# BMS_FETs.net
KiCad netlist of a schematic drawn in Altium Designer
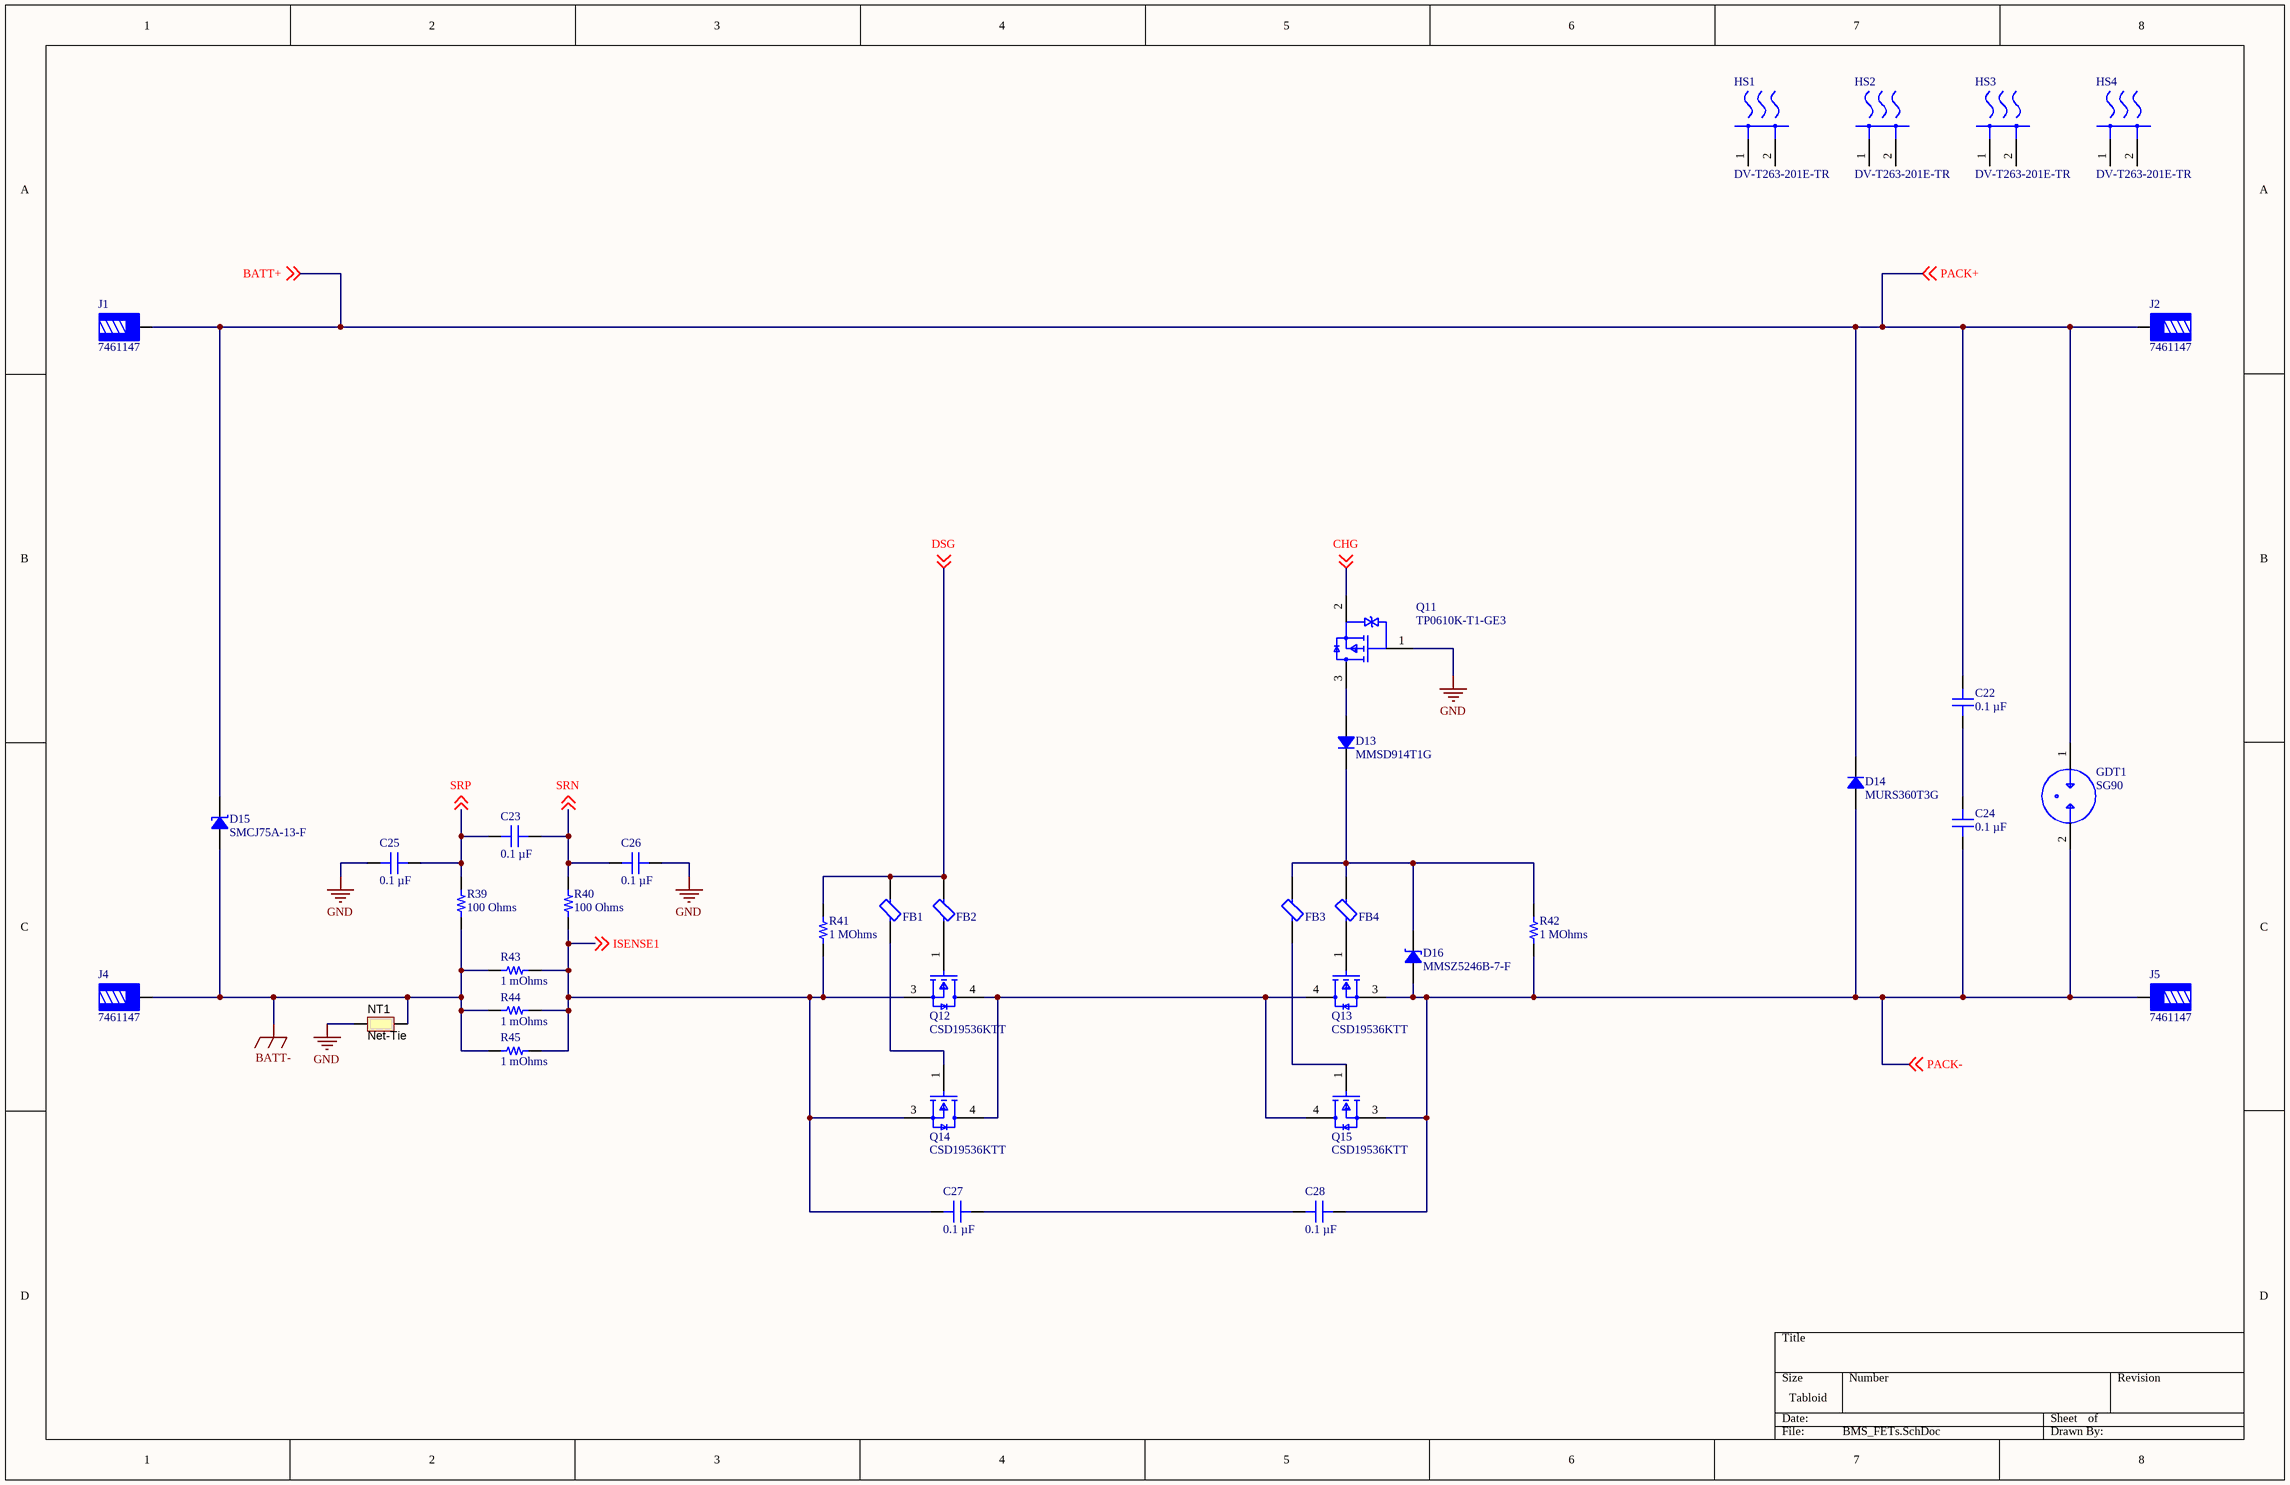
[diagram p0: BMS_FETs.SchDoc]

(export (version "E")
  (design (tool "Eeschema 10.0.6"))
  (components
    (comp (ref "C22")
      (value "0.1 µF")
      (footprint "MURATA GRM188 0603_1608")
      (description "CAP CER 0.1UF 100V X7R 0603")
      (fields
        (field (name "PART NUMBER") "GRM188R72A104KA35D")
        (field (name "CAPACITANCE") "0.1 µF")
        (field (name "MANUFACTURER") "Murata Electronics")
      )
      (libsource (lib "Celestial Altium Library - altium_library") (part "Capacitor"))
    )
    (comp (ref "C23")
      (value "0.1 µF")
      (footprint "CAP 0603_1608")
      (description "CAP CER 0.1UF 50V X7R 0603")
      (fields
        (field (name "PART NUMBER") "885012206095")
        (field (name "CAPACITANCE") "0.1 µF")
        (field (name "MANUFACTURER") "Würth Elektronik")
      )
      (libsource (lib "Celestial Altium Library - altium_library") (part "Capacitor"))
    )
    (comp (ref "C24")
      (value "0.1 µF")
      (footprint "MURATA GRM188 0603_1608")
      (description "CAP CER 0.1UF 100V X7R 0603")
      (fields
        (field (name "PART NUMBER") "GRM188R72A104KA35D")
        (field (name "CAPACITANCE") "0.1 µF")
        (field (name "MANUFACTURER") "Murata Electronics")
      )
      (libsource (lib "Celestial Altium Library - altium_library") (part "Capacitor"))
    )
    (comp (ref "C25")
      (value "0.1 µF")
      (footprint "CAP 0603_1608")
      (description "CAP CER 0.1UF 50V X7R 0603")
      (fields
        (field (name "PART NUMBER") "885012206095")
        (field (name "CAPACITANCE") "0.1 µF")
        (field (name "MANUFACTURER") "Würth Elektronik")
      )
      (libsource (lib "Celestial Altium Library - altium_library") (part "Capacitor"))
    )
    (comp (ref "C26")
      (value "0.1 µF")
      (footprint "CAP 0603_1608")
      (description "CAP CER 0.1UF 50V X7R 0603")
      (fields
        (field (name "PART NUMBER") "885012206095")
        (field (name "CAPACITANCE") "0.1 µF")
        (field (name "MANUFACTURER") "Würth Elektronik")
      )
      (libsource (lib "Celestial Altium Library - altium_library") (part "Capacitor"))
    )
    (comp (ref "C27")
      (value "0.1 µF")
      (footprint "CAP 1206_3216 - 0.8MM")
      (description "CAP CER 0.1UF 200V X7R 1206")
      (fields
        (field (name "PART NUMBER") "885342208002")
        (field (name "CAPACITANCE") "0.1 µF")
        (field (name "MANUFACTURER") "Würth Elektronik")
      )
      (libsource (lib "Celestial Altium Library - altium_library") (part "Capacitor"))
    )
    (comp (ref "C28")
      (value "0.1 µF")
      (footprint "CAP 1206_3216 - 0.8MM")
      (description "CAP CER 0.1UF 200V X7R 1206")
      (fields
        (field (name "PART NUMBER") "885342208002")
        (field (name "CAPACITANCE") "0.1 µF")
        (field (name "MANUFACTURER") "Würth Elektronik")
      )
      (libsource (lib "Celestial Altium Library - altium_library") (part "Capacitor"))
    )
    (comp (ref "D13")
      (value "MMSD914T1G")
      (footprint "SOD-123")
      (description "DIODE GEN PURP 100V 200MA SOD123")
      (fields (field (name "MANUFACTURER") "ON Semiconductor"))
      (libsource (lib "Celestial Altium Library - altium_library") (part "Diode"))
    )
    (comp (ref "D14")
      (value "MURS360T3G")
      (footprint "DO214AB SMC")
      (description "DIODE GEN PURP 600V 3A SMC")
      (fields (field (name "MANUFACTURER") "ON Semiconductor"))
      (libsource (lib "Celestial Altium Library - altium_library") (part "Diode"))
    )
    (comp (ref "D15")
      (value "SMCJ75A-13-F")
      (footprint "DO214AB SMC")
      (description "TVS DIODE 75VWM 121VC SMC")
      (fields (field (name "MANUFACTURER") "Diodes Incorporated"))
      (libsource (lib "Celestial Altium Library - altium_library") (part "DIODE TVS UNI"))
    )
    (comp (ref "D16")
      (value "MMSZ5246B-7-F")
      (footprint "SOD-123")
      (description "DIODE ZENER 16V 500MW SOD123")
      (fields (field (name "MANUFACTURER") "Diodes Incorporated") (field (name "TOLERANCE") "±5%"))
      (libsource (lib "Celestial Altium Library - altium_library") (part "Diode Zener"))
    )
    (comp (ref "FB1")
      (value "BLM18SG221TN1D")
      (footprint "FP-BLM18-0_15-t0_5-IPC_C")
      (description "Chip Ferrite Bead, 0603, 220Ω @ 100MHz, 25%, 0.04Ω, 2.5A")
      (fields (field (name "TOLERANCE") "25%"))
      (libsource (lib "BMS_FETs") (part "BLM18SG221TN1D"))
    )
    (comp (ref "FB2")
      (value "BLM18SG221TN1D")
      (footprint "FP-BLM18-0_15-t0_5-IPC_C")
      (description "Chip Ferrite Bead, 0603, 220Ω @ 100MHz, 25%, 0.04Ω, 2.5A")
      (fields (field (name "TOLERANCE") "25%"))
      (libsource (lib "BMS_FETs") (part "BLM18SG221TN1D"))
    )
    (comp (ref "FB3")
      (value "BLM18SG221TN1D")
      (footprint "FP-BLM18-0_15-t0_5-IPC_C")
      (description "Chip Ferrite Bead, 0603, 220Ω @ 100MHz, 25%, 0.04Ω, 2.5A")
      (fields (field (name "TOLERANCE") "25%"))
      (libsource (lib "BMS_FETs") (part "BLM18SG221TN1D"))
    )
    (comp (ref "FB4")
      (value "BLM18SG221TN1D")
      (footprint "FP-BLM18-0_15-t0_5-IPC_C")
      (description "Chip Ferrite Bead, 0603, 220Ω @ 100MHz, 25%, 0.04Ω, 2.5A")
      (fields (field (name "TOLERANCE") "25%"))
      (libsource (lib "BMS_FETs") (part "BLM18SG221TN1D"))
    )
    (comp (ref "GDT1")
      (value "SG90")
      (footprint "FP-SG-MFG")
      (description "GDT 90V 2KA 2 POLE SURFACE MOUNT")
      (libsource (lib "BMS_MCU") (part "SG90"))
    )
    (comp (ref "HS1")
      (value "DV-T263-201E-TR")
      (footprint "FP-DV-T263-201E-TR-MFG")
      (description "HEATSINK FOR TO-263")
      (libsource (lib "BMS_FETs") (part "DV-T263-201E-TR"))
    )
    (comp (ref "HS2")
      (value "DV-T263-201E-TR")
      (footprint "FP-DV-T263-201E-TR-MFG")
      (description "HEATSINK FOR TO-263")
      (libsource (lib "BMS_FETs") (part "DV-T263-201E-TR"))
    )
    (comp (ref "HS3")
      (value "DV-T263-201E-TR")
      (footprint "FP-DV-T263-201E-TR-MFG")
      (description "HEATSINK FOR TO-263")
      (libsource (lib "BMS_FETs") (part "DV-T263-201E-TR"))
    )
    (comp (ref "HS4")
      (value "DV-T263-201E-TR")
      (footprint "FP-DV-T263-201E-TR-MFG")
      (description "HEATSINK FOR TO-263")
      (libsource (lib "BMS_FETs") (part "DV-T263-201E-TR"))
    )
    (comp (ref "J1")
      (value "7461147")
      (footprint "7461147_chemical surface")
      (description "7461147 REDCUBE Power Element Poles, 180A, Press-Fit, M5 Internal Thread, Vertical, WP-BUFU")
      (libsource (lib "BMS_FETs") (part "7461147"))
    )
    (comp (ref "J2")
      (value "7461147")
      (footprint "7461147_chemical surface")
      (description "7461147 REDCUBE Power Element Poles, 180A, Press-Fit, M5 Internal Thread, Vertical, WP-BUFU")
      (libsource (lib "BMS_FETs") (part "7461147"))
    )
    (comp (ref "J4")
      (value "7461147")
      (footprint "7461147_chemical surface")
      (description "7461147 REDCUBE Power Element Poles, 180A, Press-Fit, M5 Internal Thread, Vertical, WP-BUFU")
      (libsource (lib "BMS_FETs") (part "7461147"))
    )
    (comp (ref "J5")
      (value "7461147")
      (footprint "7461147_chemical surface")
      (description "7461147 REDCUBE Power Element Poles, 180A, Press-Fit, M5 Internal Thread, Vertical, WP-BUFU")
      (libsource (lib "BMS_FETs") (part "7461147"))
    )
    (comp (ref "NT1")
      (value "Net-Tie")
      (footprint "Net-Tie_10mil")
      (description "Single point connection between nets.")
      (fields (field (name "SYMBOLCREATOR") "codlsc") (field (name "PUBLISHER") "Texas Instruments"))
      (libsource (lib "BMS_FETs") (part "Net-Tie"))
    )
    (comp (ref "Q11")
      (value "TP0610K-T1-GE3")
      (footprint "FP-S-03946-IPC_C")
      (description "MOSFET P-CH 60V 185MA SOT23-3")
      (libsource (lib "BMS_FETs") (part "TP0610K-T1-GE3"))
    )
    (comp (ref "Q12")
      (value "CSD19536KTT")
      (footprint "FP-CSD19536KTT-MFG")
      (description "MOSFET N-CH 100V 200A TO263")
      (fields
        (field (name "MANUFACTURER") "Texas Instruments")
        (field (name "OCTOPART") "https://octopart.com/csd19536ktt-texas+instruments-57155051")
      )
      (libsource (lib "BMS_FETs") (part "CSD19536KTT"))
    )
    (comp (ref "Q13")
      (value "CSD19536KTT")
      (footprint "FP-CSD19536KTT-MFG")
      (description "MOSFET N-CH 100V 200A TO263")
      (fields
        (field (name "MANUFACTURER") "Texas Instruments")
        (field (name "OCTOPART") "https://octopart.com/csd19536ktt-texas+instruments-57155051")
      )
      (libsource (lib "BMS_FETs") (part "CSD19536KTT"))
    )
    (comp (ref "Q14")
      (value "CSD19536KTT")
      (footprint "FP-CSD19536KTT-MFG")
      (description "MOSFET N-CH 100V 200A TO263")
      (fields
        (field (name "MANUFACTURER") "Texas Instruments")
        (field (name "OCTOPART") "https://octopart.com/csd19536ktt-texas+instruments-57155051")
      )
      (libsource (lib "BMS_FETs") (part "CSD19536KTT"))
    )
    (comp (ref "Q15")
      (value "CSD19536KTT")
      (footprint "FP-CSD19536KTT-MFG")
      (description "MOSFET N-CH 100V 200A TO263")
      (fields
        (field (name "MANUFACTURER") "Texas Instruments")
        (field (name "OCTOPART") "https://octopart.com/csd19536ktt-texas+instruments-57155051")
      )
      (libsource (lib "BMS_FETs") (part "CSD19536KTT"))
    )
    (comp (ref "R39")
      (value "100 Ohms")
      (footprint "RES 0805_2012")
      (description "RES SMD 100 OHM 1% 1/8W 0805")
      (fields (field (name "PART NUMBER") "CRCW0805100RFKEA") (field (name "MANUFACTURER") "Vishay Dale"))
      (libsource (lib "Celestial Altium Library - altium_library") (part "Resistor"))
    )
    (comp (ref "R40")
      (value "100 Ohms")
      (footprint "RES 0805_2012")
      (description "RES SMD 100 OHM 1% 1/8W 0805")
      (fields (field (name "PART NUMBER") "CRCW0805100RFKEA") (field (name "MANUFACTURER") "Vishay Dale"))
      (libsource (lib "Celestial Altium Library - altium_library") (part "Resistor"))
    )
    (comp (ref "R41")
      (value "1 MOhms")
      (footprint "RES 0603_1608")
      (description "RES 1M OHM 5% 1/10W 0603")
      (fields
        (field (name "PART NUMBER") "RMCF0603JT1M00")
        (field (name "MANUFACTURER") "Stackpole Electronics Inc")
      )
      (libsource (lib "Celestial Altium Library - altium_library") (part "Resistor"))
    )
    (comp (ref "R42")
      (value "1 MOhms")
      (footprint "RES 0603_1608")
      (description "RES 1M OHM 5% 1/10W 0603")
      (fields
        (field (name "PART NUMBER") "RMCF0603JT1M00")
        (field (name "MANUFACTURER") "Stackpole Electronics Inc")
      )
      (libsource (lib "Celestial Altium Library - altium_library") (part "Resistor"))
    )
    (comp (ref "R43")
      (value "1 mOhms")
      (footprint "RES 2512_6432")
      (description "RES 0.001 OHM 1% 5W 2512")
      (fields (field (name "PART NUMBER") "WSLF25121L000FEA") (field (name "MANUFACTURER") "Vishay Dale"))
      (libsource (lib "Celestial Altium Library - altium_library") (part "Resistor"))
    )
    (comp (ref "R44")
      (value "1 mOhms")
      (footprint "RES 2512_6432")
      (description "RES 0.001 OHM 1% 5W 2512")
      (fields (field (name "PART NUMBER") "WSLF25121L000FEA") (field (name "MANUFACTURER") "Vishay Dale"))
      (libsource (lib "Celestial Altium Library - altium_library") (part "Resistor"))
    )
    (comp (ref "R45")
      (value "1 mOhms")
      (footprint "RES 2512_6432")
      (description "RES 0.001 OHM 1% 5W 2512")
      (fields (field (name "PART NUMBER") "WSLF25121L000FEA") (field (name "MANUFACTURER") "Vishay Dale"))
      (libsource (lib "Celestial Altium Library - altium_library") (part "Resistor"))
    )
  )
  (nets
    (net (code "1") (name "BATT+") (class "Default")
      (node (ref "C22") (pin "2") (pinfunction "2_2") (pintype "passive"))
      (node (ref "D14") (pin "2") (pinfunction "2_2") (pintype "passive"))
      (node (ref "D15") (pin "2") (pinfunction "2_2") (pintype "passive"))
      (node (ref "GDT1") (pin "1") (pinfunction "1_1") (pintype "passive"))
      (node (ref "J1") (pin "1") (pinfunction "1_1") (pintype "passive"))
      (node (ref "J2") (pin "1") (pinfunction "1_1") (pintype "passive"))
    )
    (net (code "2") (name "BATT-") (class "Default")
      (node (ref "D15") (pin "1") (pinfunction "1_1") (pintype "passive"))
      (node (ref "J4") (pin "1") (pinfunction "1_1") (pintype "passive"))
      (node (ref "NT1") (pin "2") (pinfunction "2_2") (pintype "passive"))
      (node (ref "R39") (pin "1") (pinfunction "1_1") (pintype "passive"))
      (node (ref "R43") (pin "1") (pinfunction "1_1") (pintype "passive"))
      (node (ref "R44") (pin "1") (pinfunction "1_1") (pintype "passive"))
      (node (ref "R45") (pin "1") (pinfunction "1_1") (pintype "passive"))
    )
    (net (code "3") (name "CHG") (class "Default")
      (node (ref "Q11") (pin "2") (pinfunction "S_2") (pintype "passive"))
    )
    (net (code "4") (name "DSG") (class "Default")
      (node (ref "FB1") (pin "2") (pinfunction "2_2") (pintype "passive"))
      (node (ref "FB2") (pin "2") (pinfunction "2_2") (pintype "passive"))
      (node (ref "R41") (pin "2") (pinfunction "2_2") (pintype "passive"))
    )
    (net (code "5") (name "GND") (class "Default")
      (node (ref "C25") (pin "1") (pinfunction "1_1") (pintype "passive"))
      (node (ref "C26") (pin "2") (pinfunction "2_2") (pintype "passive"))
      (node (ref "NT1") (pin "1") (pinfunction "1_1") (pintype "passive"))
      (node (ref "Q11") (pin "1") (pinfunction "G_1") (pintype "passive"))
    )
    (net (code "6") (name "ISENSE1") (class "Default")
      (node (ref "C27") (pin "1") (pinfunction "1_1") (pintype "passive"))
      (node (ref "Q12") (pin "3") (pinfunction "Source_3") (pintype "passive"))
      (node (ref "Q14") (pin "3") (pinfunction "Source_3") (pintype "passive"))
      (node (ref "R40") (pin "1") (pinfunction "1_1") (pintype "passive"))
      (node (ref "R41") (pin "1") (pinfunction "1_1") (pintype "passive"))
      (node (ref "R43") (pin "2") (pinfunction "2_2") (pintype "passive"))
      (node (ref "R44") (pin "2") (pinfunction "2_2") (pintype "passive"))
      (node (ref "R45") (pin "2") (pinfunction "2_2") (pintype "passive"))
    )
    (net (code "7") (name "Net-(C22-Pad1)") (class "Default")
      (node (ref "C22") (pin "1") (pinfunction "1_1") (pintype "passive"))
      (node (ref "C24") (pin "2") (pinfunction "2_2") (pintype "passive"))
    )
    (net (code "8") (name "Net-(C27-Pad2)") (class "Default")
      (node (ref "C27") (pin "2") (pinfunction "2_2") (pintype "passive"))
      (node (ref "C28") (pin "1") (pinfunction "1_1") (pintype "passive"))
    )
    (net (code "9") (name "Net-(D13-Pad2)") (class "Default")
      (node (ref "D13") (pin "2") (pinfunction "2_2") (pintype "passive"))
      (node (ref "D16") (pin "2") (pinfunction "2_2") (pintype "passive"))
      (node (ref "FB3") (pin "2") (pinfunction "2_2") (pintype "passive"))
      (node (ref "FB4") (pin "2") (pinfunction "2_2") (pintype "passive"))
      (node (ref "R42") (pin "2") (pinfunction "2_2") (pintype "passive"))
    )
    (net (code "10") (name "Net-(Q11-D)") (class "Default")
      (node (ref "D13") (pin "1") (pinfunction "1_1") (pintype "passive"))
      (node (ref "Q11") (pin "3") (pinfunction "D_3") (pintype "passive"))
    )
    (net (code "11") (name "Net-(Q12-Drain)") (class "Default")
      (node (ref "Q12") (pin "4") (pinfunction "Drain_4") (pintype "passive"))
      (node (ref "Q13") (pin "4") (pinfunction "Drain_4") (pintype "passive"))
      (node (ref "Q14") (pin "4") (pinfunction "Drain_4") (pintype "passive"))
      (node (ref "Q15") (pin "4") (pinfunction "Drain_4") (pintype "passive"))
    )
    (net (code "12") (name "Net-(Q12-Gate)") (class "Default")
      (node (ref "FB2") (pin "1") (pinfunction "1_1") (pintype "passive"))
      (node (ref "Q12") (pin "1") (pinfunction "Gate_1") (pintype "passive"))
    )
    (net (code "13") (name "Net-(Q13-Gate)") (class "Default")
      (node (ref "FB4") (pin "1") (pinfunction "1_1") (pintype "passive"))
      (node (ref "Q13") (pin "1") (pinfunction "Gate_1") (pintype "passive"))
    )
    (net (code "14") (name "Net-(Q14-Gate)") (class "Default")
      (node (ref "FB1") (pin "1") (pinfunction "1_1") (pintype "passive"))
      (node (ref "Q14") (pin "1") (pinfunction "Gate_1") (pintype "passive"))
    )
    (net (code "15") (name "Net-(Q15-Gate)") (class "Default")
      (node (ref "FB3") (pin "1") (pinfunction "1_1") (pintype "passive"))
      (node (ref "Q15") (pin "1") (pinfunction "Gate_1") (pintype "passive"))
    )
    (net (code "16") (name "PACK-") (class "Default")
      (node (ref "C24") (pin "1") (pinfunction "1_1") (pintype "passive"))
      (node (ref "C28") (pin "2") (pinfunction "2_2") (pintype "passive"))
      (node (ref "D14") (pin "1") (pinfunction "1_1") (pintype "passive"))
      (node (ref "D16") (pin "1") (pinfunction "1_1") (pintype "passive"))
      (node (ref "GDT1") (pin "2") (pinfunction "2_2") (pintype "passive"))
      (node (ref "J5") (pin "1") (pinfunction "1_1") (pintype "passive"))
      (node (ref "Q13") (pin "3") (pinfunction "Source_3") (pintype "passive"))
      (node (ref "Q15") (pin "3") (pinfunction "Source_3") (pintype "passive"))
      (node (ref "R42") (pin "1") (pinfunction "1_1") (pintype "passive"))
    )
    (net (code "17") (name "SRN") (class "Default")
      (node (ref "C23") (pin "2") (pinfunction "2_2") (pintype "passive"))
      (node (ref "C26") (pin "1") (pinfunction "1_1") (pintype "passive"))
      (node (ref "R40") (pin "2") (pinfunction "2_2") (pintype "passive"))
    )
    (net (code "18") (name "SRP") (class "Default")
      (node (ref "C23") (pin "1") (pinfunction "1_1") (pintype "passive"))
      (node (ref "C25") (pin "2") (pinfunction "2_2") (pintype "passive"))
      (node (ref "R39") (pin "2") (pinfunction "2_2") (pintype "passive"))
    )
    (net (code "19") (name "unconnected-(HS1-MNT_1-Pad1)") (class "Default")
      (node (ref "HS1") (pin "1") (pinfunction "MNT_1_1") (pintype "passive"))
    )
    (net (code "20") (name "unconnected-(HS1-MNT_2-Pad2)") (class "Default")
      (node (ref "HS1") (pin "2") (pinfunction "MNT_2_2") (pintype "passive"))
    )
    (net (code "21") (name "unconnected-(HS2-MNT_1-Pad1)") (class "Default")
      (node (ref "HS2") (pin "1") (pinfunction "MNT_1_1") (pintype "passive"))
    )
    (net (code "22") (name "unconnected-(HS2-MNT_2-Pad2)") (class "Default")
      (node (ref "HS2") (pin "2") (pinfunction "MNT_2_2") (pintype "passive"))
    )
    (net (code "23") (name "unconnected-(HS3-MNT_1-Pad1)") (class "Default")
      (node (ref "HS3") (pin "1") (pinfunction "MNT_1_1") (pintype "passive"))
    )
    (net (code "24") (name "unconnected-(HS3-MNT_2-Pad2)") (class "Default")
      (node (ref "HS3") (pin "2") (pinfunction "MNT_2_2") (pintype "passive"))
    )
    (net (code "25") (name "unconnected-(HS4-MNT_1-Pad1)") (class "Default")
      (node (ref "HS4") (pin "1") (pinfunction "MNT_1_1") (pintype "passive"))
    )
    (net (code "26") (name "unconnected-(HS4-MNT_2-Pad2)") (class "Default")
      (node (ref "HS4") (pin "2") (pinfunction "MNT_2_2") (pintype "passive"))
    )
  )
)
